# deeds-c3.net
KiCad netlist of a schematic drawn in EAGLE
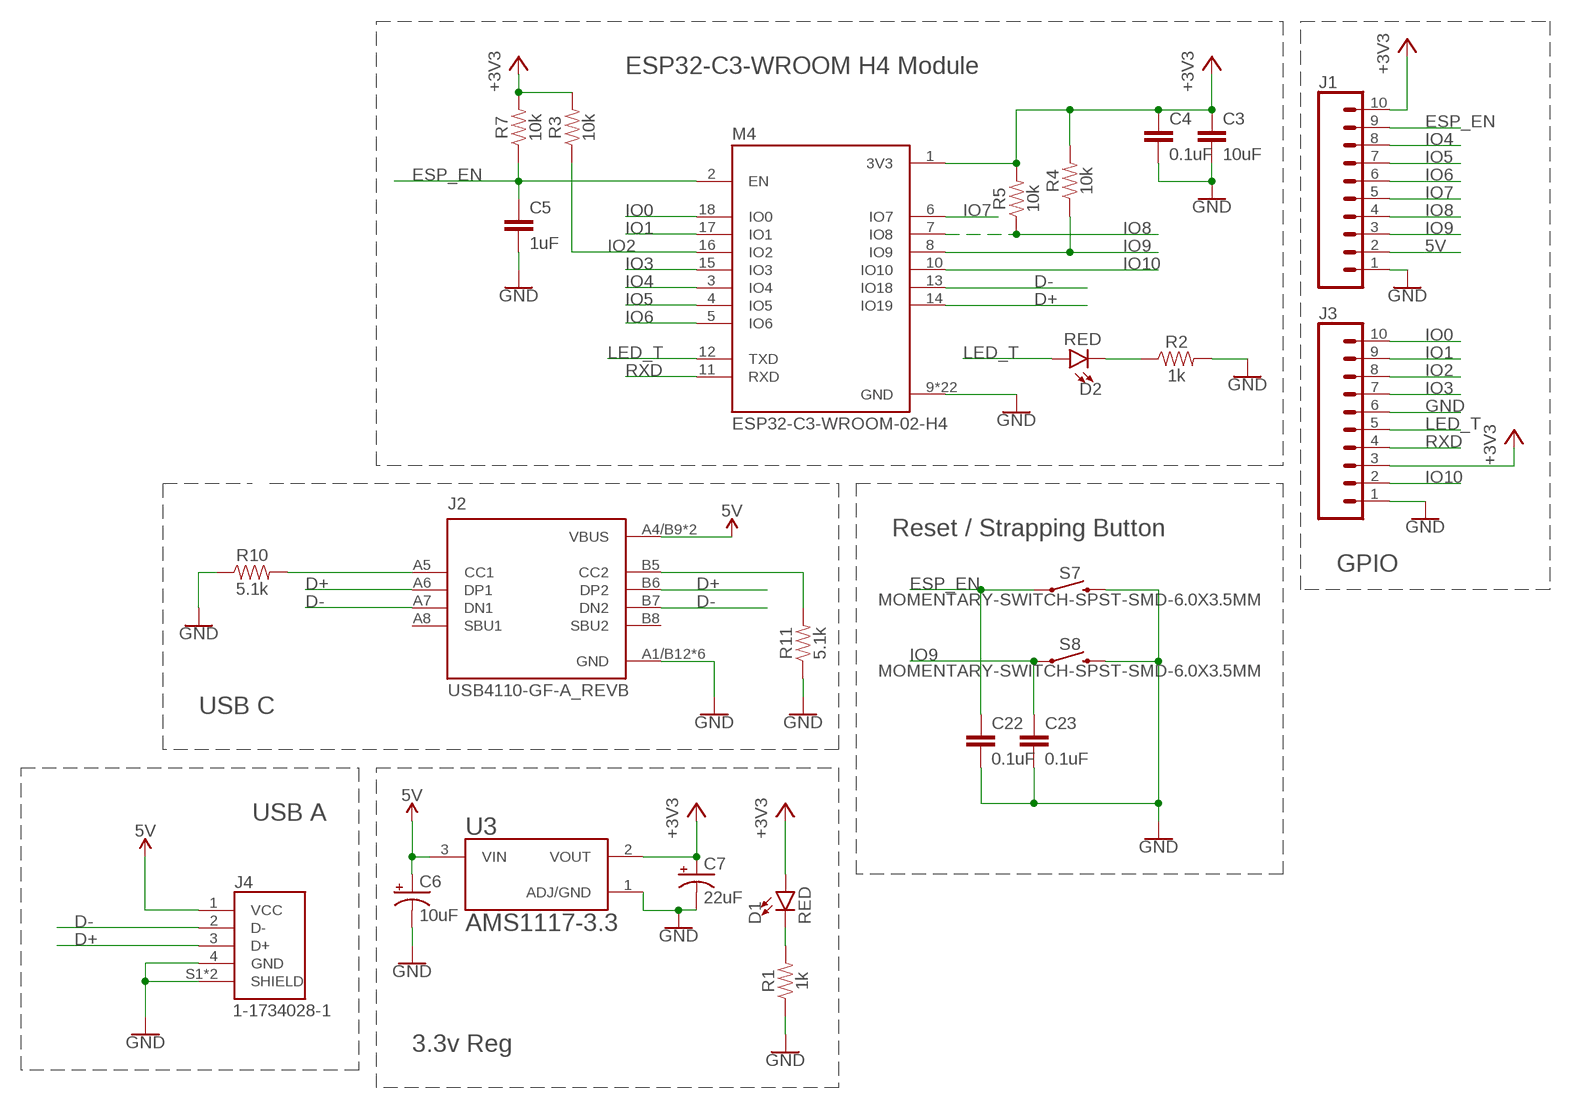
[diagram p0: schematic, sheet 1]

(export (version "E")
  (design (tool "Eeschema 10.0.6"))
  (components
    (comp (ref "C3")
      (value "10uF")
      (footprint "eagle-import:0603")
      (libsource (lib "eagle-import") (part "10UF-0603-6.3V-20%"))
    )
    (comp (ref "C4")
      (value "0.1uF")
      (footprint "eagle-import:0603")
      (libsource (lib "eagle-import") (part "10UF-0603-6.3V-20%"))
    )
    (comp (ref "C5")
      (value "1uF")
      (footprint "eagle-import:0603")
      (libsource (lib "eagle-import") (part "10UF-0603-6.3V-20%"))
    )
    (comp (ref "C6")
      (value "10uF")
      (footprint "eagle-import:EIA3216")
      (libsource (lib "eagle-import") (part "10UF-POLAR-EIA3216-16V-10%(TANT)"))
    )
    (comp (ref "C7")
      (value "22uF")
      (footprint "eagle-import:EIA3216")
      (libsource (lib "eagle-import") (part "10UF-POLAR-EIA3216-16V-10%(TANT)"))
    )
    (comp (ref "C22")
      (value "0.1uF")
      (footprint "eagle-import:0603")
      (libsource (lib "eagle-import") (part "0.1UF-0603-25V-(+80/-20%)"))
    )
    (comp (ref "C23")
      (value "0.1uF")
      (footprint "eagle-import:0603")
      (libsource (lib "eagle-import") (part "0.1UF-0603-25V-(+80/-20%)"))
    )
    (comp (ref "D1")
      (value "RED")
      (footprint "eagle-import:LED-0603")
      (libsource (lib "eagle-import") (part "LED-RED0603"))
    )
    (comp (ref "D2")
      (value "RED")
      (footprint "eagle-import:LED-0603")
      (libsource (lib "eagle-import") (part "LED-RED0603"))
    )
    (comp (ref "J1")
      (value "CONN_10\"")
      (footprint "eagle-import:1X10")
      (libsource (lib "eagle-import") (part "CONN_10{dblquote}"))
    )
    (comp (ref "J2")
      (value "USB4110-GF-A_REVB")
      (footprint "eagle-import:GCT_USB4110-GF-A_REVB")
      (fields (field (name "MF") "GCT") (field (name "MP") "USB4110-GF-A"))
      (libsource (lib "eagle-import") (part "USB4110-GF-A_REVB"))
    )
    (comp (ref "J3")
      (value "CONN_10\"")
      (footprint "eagle-import:1X10")
      (libsource (lib "eagle-import") (part "CONN_10{dblquote}"))
    )
    (comp (ref "J4")
      (value "1-1734028-1")
      (footprint "eagle-import:TE_1-1734028-1")
      (fields (field (name "MF") "TE Connectivity"))
      (libsource (lib "eagle-import") (part "1-1734028-1"))
    )
    (comp (ref "M4")
      (value "ESP32-C3-WROOM-02-H4")
      (footprint "eagle-import:MODULE_ESP32-C3-WROOM-02-H4")
      (fields (field (name "MF") "Espressif Systems"))
      (libsource (lib "eagle-import") (part "ESP32-C3-WROOM-02-H4"))
    )
    (comp (ref "R1")
      (value "1k")
      (footprint "eagle-import:0603")
      (libsource (lib "eagle-import") (part "1KOHM-0603-1/10W-1%"))
    )
    (comp (ref "R2")
      (value "1k")
      (footprint "eagle-import:0603")
      (libsource (lib "eagle-import") (part "1KOHM-0603-1/10W-1%"))
    )
    (comp (ref "R3")
      (value "10k")
      (footprint "eagle-import:0603")
      (libsource (lib "eagle-import") (part "1KOHM-0603-1/10W-1%"))
    )
    (comp (ref "R4")
      (value "10k")
      (footprint "eagle-import:0603")
      (libsource (lib "eagle-import") (part "1KOHM-0603-1/10W-1%"))
    )
    (comp (ref "R5")
      (value "10k")
      (footprint "eagle-import:0603")
      (libsource (lib "eagle-import") (part "1KOHM-0603-1/10W-1%"))
    )
    (comp (ref "R7")
      (value "10k")
      (footprint "eagle-import:0603")
      (libsource (lib "eagle-import") (part "1KOHM-0603-1/10W-1%"))
    )
    (comp (ref "R10")
      (value "5.1k")
      (footprint "eagle-import:0603")
      (libsource (lib "eagle-import") (part "1KOHM-0603-1/10W-1%"))
    )
    (comp (ref "R11")
      (value "5.1k")
      (footprint "eagle-import:0603")
      (libsource (lib "eagle-import") (part "1KOHM-0603-1/10W-1%"))
    )
    (comp (ref "S7")
      (value "MOMENTARY-SWITCH-SPST-SMD-6.0X3.5MM")
      (footprint "eagle-import:TACTILE_SWITCH_SMD_6.0X3.5MM")
      (libsource (lib "eagle-import") (part "MOMENTARY-SWITCH-SPST-SMD-6.0X3.5MM"))
    )
    (comp (ref "S8")
      (value "MOMENTARY-SWITCH-SPST-SMD-6.0X3.5MM")
      (footprint "eagle-import:TACTILE_SWITCH_SMD_6.0X3.5MM")
      (libsource (lib "eagle-import") (part "MOMENTARY-SWITCH-SPST-SMD-6.0X3.5MM"))
    )
    (comp (ref "U3")
      (value "AMS1117-3.3")
      (footprint "eagle-import:SOT229P700X180-4N")
      (fields (field (name "MF") "AMD"))
      (libsource (lib "eagle-import") (part "AMS1117-3.3"))
    )
  )
  (nets
    (net (code "1") (name "+3V3") (class "Default")
      (node (ref "C3") (pin "1") (pinfunction "1_1") (pintype "passive"))
      (node (ref "C4") (pin "1") (pinfunction "1_1") (pintype "passive"))
      (node (ref "C7") (pin "+") (pinfunction "+_+") (pintype "passive"))
      (node (ref "D1") (pin "A") (pinfunction "A_A") (pintype "passive"))
      (node (ref "J1") (pin "10") (pinfunction "10_10") (pintype "passive"))
      (node (ref "J3") (pin "3") (pinfunction "3_3") (pintype "passive"))
      (node (ref "M4") (pin "1") (pinfunction "3V3_1") (pintype "power_in"))
      (node (ref "R3") (pin "2") (pinfunction "2_2") (pintype "passive"))
      (node (ref "R4") (pin "2") (pinfunction "2_2") (pintype "passive"))
      (node (ref "R5") (pin "2") (pinfunction "2_2") (pintype "passive"))
      (node (ref "R7") (pin "2") (pinfunction "2_2") (pintype "passive"))
      (node (ref "U3") (pin "2") (pinfunction "VOUT_2") (pintype "output"))
    )
    (net (code "2") (name "/D+") (class "Default")
      (node (ref "J2") (pin "A6") (pinfunction "DP1_A6") (pintype "bidirectional"))
      (node (ref "J2") (pin "B6") (pinfunction "DP2_B6") (pintype "bidirectional"))
      (node (ref "J4") (pin "3") (pinfunction "D+_3") (pintype "bidirectional"))
      (node (ref "M4") (pin "14") (pinfunction "IO19_14") (pintype "bidirectional"))
    )
    (net (code "3") (name "/D-") (class "Default")
      (node (ref "J2") (pin "A7") (pinfunction "DN1_A7") (pintype "bidirectional"))
      (node (ref "J2") (pin "B7") (pinfunction "DN2_B7") (pintype "bidirectional"))
      (node (ref "J4") (pin "2") (pinfunction "D-_2") (pintype "bidirectional"))
      (node (ref "M4") (pin "13") (pinfunction "IO18_13") (pintype "bidirectional"))
    )
    (net (code "4") (name "/ESP_EN") (class "Default")
      (node (ref "C22") (pin "1") (pinfunction "1_1") (pintype "passive"))
      (node (ref "C5") (pin "1") (pinfunction "1_1") (pintype "passive"))
      (node (ref "J1") (pin "9") (pinfunction "9_9") (pintype "passive"))
      (node (ref "M4") (pin "2") (pinfunction "EN_2") (pintype "input"))
      (node (ref "R7") (pin "1") (pinfunction "1_1") (pintype "passive"))
      (node (ref "S7") (pin "1") (pinfunction "1_1") (pintype "passive"))
    )
    (net (code "5") (name "/IO0") (class "Default")
      (node (ref "J3") (pin "10") (pinfunction "10_10") (pintype "passive"))
      (node (ref "M4") (pin "18") (pinfunction "IO0_18") (pintype "bidirectional"))
    )
    (net (code "6") (name "/IO1") (class "Default")
      (node (ref "J3") (pin "9") (pinfunction "9_9") (pintype "passive"))
      (node (ref "M4") (pin "17") (pinfunction "IO1_17") (pintype "bidirectional"))
    )
    (net (code "7") (name "/IO2") (class "Default")
      (node (ref "J3") (pin "8") (pinfunction "8_8") (pintype "passive"))
      (node (ref "M4") (pin "16") (pinfunction "IO2_16") (pintype "bidirectional"))
      (node (ref "R3") (pin "1") (pinfunction "1_1") (pintype "passive"))
    )
    (net (code "8") (name "/IO3") (class "Default")
      (node (ref "J3") (pin "7") (pinfunction "7_7") (pintype "passive"))
      (node (ref "M4") (pin "15") (pinfunction "IO3_15") (pintype "bidirectional"))
    )
    (net (code "9") (name "/IO4") (class "Default")
      (node (ref "J1") (pin "8") (pinfunction "8_8") (pintype "passive"))
      (node (ref "M4") (pin "3") (pinfunction "IO4_3") (pintype "bidirectional"))
    )
    (net (code "10") (name "/IO5") (class "Default")
      (node (ref "J1") (pin "7") (pinfunction "7_7") (pintype "passive"))
      (node (ref "M4") (pin "4") (pinfunction "IO5_4") (pintype "bidirectional"))
    )
    (net (code "11") (name "/IO6") (class "Default")
      (node (ref "J1") (pin "6") (pinfunction "6_6") (pintype "passive"))
      (node (ref "M4") (pin "5") (pinfunction "IO6_5") (pintype "bidirectional"))
    )
    (net (code "12") (name "/IO7") (class "Default")
      (node (ref "J1") (pin "5") (pinfunction "5_5") (pintype "passive"))
      (node (ref "M4") (pin "6") (pinfunction "IO7_6") (pintype "bidirectional"))
    )
    (net (code "13") (name "/IO8") (class "Default")
      (node (ref "J1") (pin "4") (pinfunction "4_4") (pintype "passive"))
      (node (ref "M4") (pin "7") (pinfunction "IO8_7") (pintype "bidirectional"))
      (node (ref "R5") (pin "1") (pinfunction "1_1") (pintype "passive"))
    )
    (net (code "14") (name "/IO9") (class "Default")
      (node (ref "C23") (pin "1") (pinfunction "1_1") (pintype "passive"))
      (node (ref "J1") (pin "3") (pinfunction "3_3") (pintype "passive"))
      (node (ref "M4") (pin "8") (pinfunction "IO9_8") (pintype "bidirectional"))
      (node (ref "R4") (pin "1") (pinfunction "1_1") (pintype "passive"))
      (node (ref "S8") (pin "1") (pinfunction "1_1") (pintype "passive"))
    )
    (net (code "15") (name "/IO10") (class "Default")
      (node (ref "J3") (pin "2") (pinfunction "2_2") (pintype "passive"))
      (node (ref "M4") (pin "10") (pinfunction "IO10_10") (pintype "bidirectional"))
    )
    (net (code "16") (name "/LED_T") (class "Default")
      (node (ref "D2") (pin "A") (pinfunction "A_A") (pintype "passive"))
      (node (ref "J3") (pin "5") (pinfunction "5_5") (pintype "passive"))
      (node (ref "M4") (pin "12") (pinfunction "TXD_12") (pintype "bidirectional"))
    )
    (net (code "17") (name "/RXD") (class "Default")
      (node (ref "J3") (pin "4") (pinfunction "4_4") (pintype "passive"))
      (node (ref "M4") (pin "11") (pinfunction "RXD_11") (pintype "bidirectional"))
    )
    (net (code "18") (name "5V") (class "Default")
      (node (ref "C6") (pin "+") (pinfunction "+_+") (pintype "passive"))
      (node (ref "J1") (pin "2") (pinfunction "2_2") (pintype "passive"))
      (node (ref "J2") (pin "A4/B9") (pinfunction "VBUS_A4/B9") (pintype "power_in"))
      (node (ref "J2") (pin "B4/A9") (pinfunction "VBUS_B4/A9") (pintype "power_in"))
      (node (ref "J4") (pin "1") (pinfunction "VCC_1") (pintype "power_in"))
      (node (ref "U3") (pin "3") (pinfunction "VIN_3") (pintype "input"))
    )
    (net (code "19") (name "GND") (class "Default")
      (node (ref "C22") (pin "2") (pinfunction "2_2") (pintype "passive"))
      (node (ref "C23") (pin "2") (pinfunction "2_2") (pintype "passive"))
      (node (ref "C3") (pin "2") (pinfunction "2_2") (pintype "passive"))
      (node (ref "C4") (pin "2") (pinfunction "2_2") (pintype "passive"))
      (node (ref "C5") (pin "2") (pinfunction "2_2") (pintype "passive"))
      (node (ref "C6") (pin "-") (pinfunction "-_-") (pintype "passive"))
      (node (ref "C7") (pin "-") (pinfunction "-_-") (pintype "passive"))
      (node (ref "J1") (pin "1") (pinfunction "1_1") (pintype "passive"))
      (node (ref "J2") (pin "A1/B12") (pinfunction "GND_A1/B12") (pintype "power_in"))
      (node (ref "J2") (pin "B1/A12") (pinfunction "GND_B1/A12") (pintype "power_in"))
      (node (ref "J2") (pin "S1") (pinfunction "GND_S1") (pintype "power_in"))
      (node (ref "J2") (pin "S2") (pinfunction "GND_S2") (pintype "power_in"))
      (node (ref "J2") (pin "S3") (pinfunction "GND_S3") (pintype "power_in"))
      (node (ref "J2") (pin "S4") (pinfunction "GND_S4") (pintype "power_in"))
      (node (ref "J3") (pin "1") (pinfunction "1_1") (pintype "passive"))
      (node (ref "J3") (pin "6") (pinfunction "6_6") (pintype "passive"))
      (node (ref "J4") (pin "4") (pinfunction "GND_4") (pintype "power_in"))
      (node (ref "J4") (pin "S1") (pinfunction "SHIELD_S1") (pintype "power_in"))
      (node (ref "J4") (pin "S2") (pinfunction "SHIELD_S2") (pintype "power_in"))
      (node (ref "M4") (pin "19") (pinfunction "GND_19") (pintype "power_in"))
      (node (ref "M4") (pin "20") (pinfunction "GND_20") (pintype "power_in"))
      (node (ref "M4") (pin "21") (pinfunction "GND_21") (pintype "power_in"))
      (node (ref "M4") (pin "22") (pinfunction "GND_22") (pintype "power_in"))
      (node (ref "M4") (pin "23") (pinfunction "GND_23") (pintype "power_in"))
      (node (ref "M4") (pin "24") (pinfunction "GND_24") (pintype "power_in"))
      (node (ref "M4") (pin "25") (pinfunction "GND_25") (pintype "power_in"))
      (node (ref "M4") (pin "26") (pinfunction "GND_26") (pintype "power_in"))
      (node (ref "M4") (pin "27") (pinfunction "GND_27") (pintype "power_in"))
      (node (ref "M4") (pin "28") (pinfunction "GND_28") (pintype "power_in"))
      (node (ref "M4") (pin "29") (pinfunction "GND_29") (pintype "power_in"))
      (node (ref "M4") (pin "30") (pinfunction "GND_30") (pintype "power_in"))
      (node (ref "M4") (pin "31") (pinfunction "GND_31") (pintype "power_in"))
      (node (ref "M4") (pin "32") (pinfunction "GND_32") (pintype "power_in"))
      (node (ref "M4") (pin "33") (pinfunction "GND_33") (pintype "power_in"))
      (node (ref "M4") (pin "34") (pinfunction "GND_34") (pintype "power_in"))
      (node (ref "M4") (pin "35") (pinfunction "GND_35") (pintype "power_in"))
      (node (ref "M4") (pin "36") (pinfunction "GND_36") (pintype "power_in"))
      (node (ref "M4") (pin "37") (pinfunction "GND_37") (pintype "power_in"))
      (node (ref "M4") (pin "38") (pinfunction "GND_38") (pintype "power_in"))
      (node (ref "M4") (pin "39") (pinfunction "GND_39") (pintype "power_in"))
      (node (ref "M4") (pin "9") (pinfunction "GND_9") (pintype "power_in"))
      (node (ref "R1") (pin "1") (pinfunction "1_1") (pintype "passive"))
      (node (ref "R10") (pin "1") (pinfunction "1_1") (pintype "passive"))
      (node (ref "R11") (pin "1") (pinfunction "1_1") (pintype "passive"))
      (node (ref "R2") (pin "2") (pinfunction "2_2") (pintype "passive"))
      (node (ref "S7") (pin "2") (pinfunction "2_2") (pintype "passive"))
      (node (ref "S8") (pin "2") (pinfunction "2_2") (pintype "passive"))
      (node (ref "U3") (pin "1") (pinfunction "ADJ/GND_1") (pintype "power_in"))
    )
    (net (code "20") (name "Net-(D1-PadC)") (class "Default")
      (node (ref "D1") (pin "C") (pinfunction "C_C") (pintype "passive"))
      (node (ref "R1") (pin "2") (pinfunction "2_2") (pintype "passive"))
    )
    (net (code "21") (name "Net-(D2-PadC)") (class "Default")
      (node (ref "D2") (pin "C") (pinfunction "C_C") (pintype "passive"))
      (node (ref "R2") (pin "1") (pinfunction "1_1") (pintype "passive"))
    )
    (net (code "22") (name "Net-(J2-CC1)") (class "Default")
      (node (ref "J2") (pin "A5") (pinfunction "CC1_A5") (pintype "bidirectional"))
      (node (ref "R10") (pin "2") (pinfunction "2_2") (pintype "passive"))
    )
    (net (code "23") (name "Net-(J2-CC2)") (class "Default")
      (node (ref "J2") (pin "B5") (pinfunction "CC2_B5") (pintype "bidirectional"))
      (node (ref "R11") (pin "2") (pinfunction "2_2") (pintype "passive"))
    )
    (net (code "24") (name "unconnected-(J2-SBU1-PadA8)") (class "Default")
      (node (ref "J2") (pin "A8") (pinfunction "SBU1_A8") (pintype "bidirectional"))
    )
    (net (code "25") (name "unconnected-(J2-SBU2-PadB8)") (class "Default")
      (node (ref "J2") (pin "B8") (pinfunction "SBU2_B8") (pintype "bidirectional"))
    )
  )
)
